# SparkFun_BadgerStick.net
KiCad netlist of a schematic drawn in EAGLE
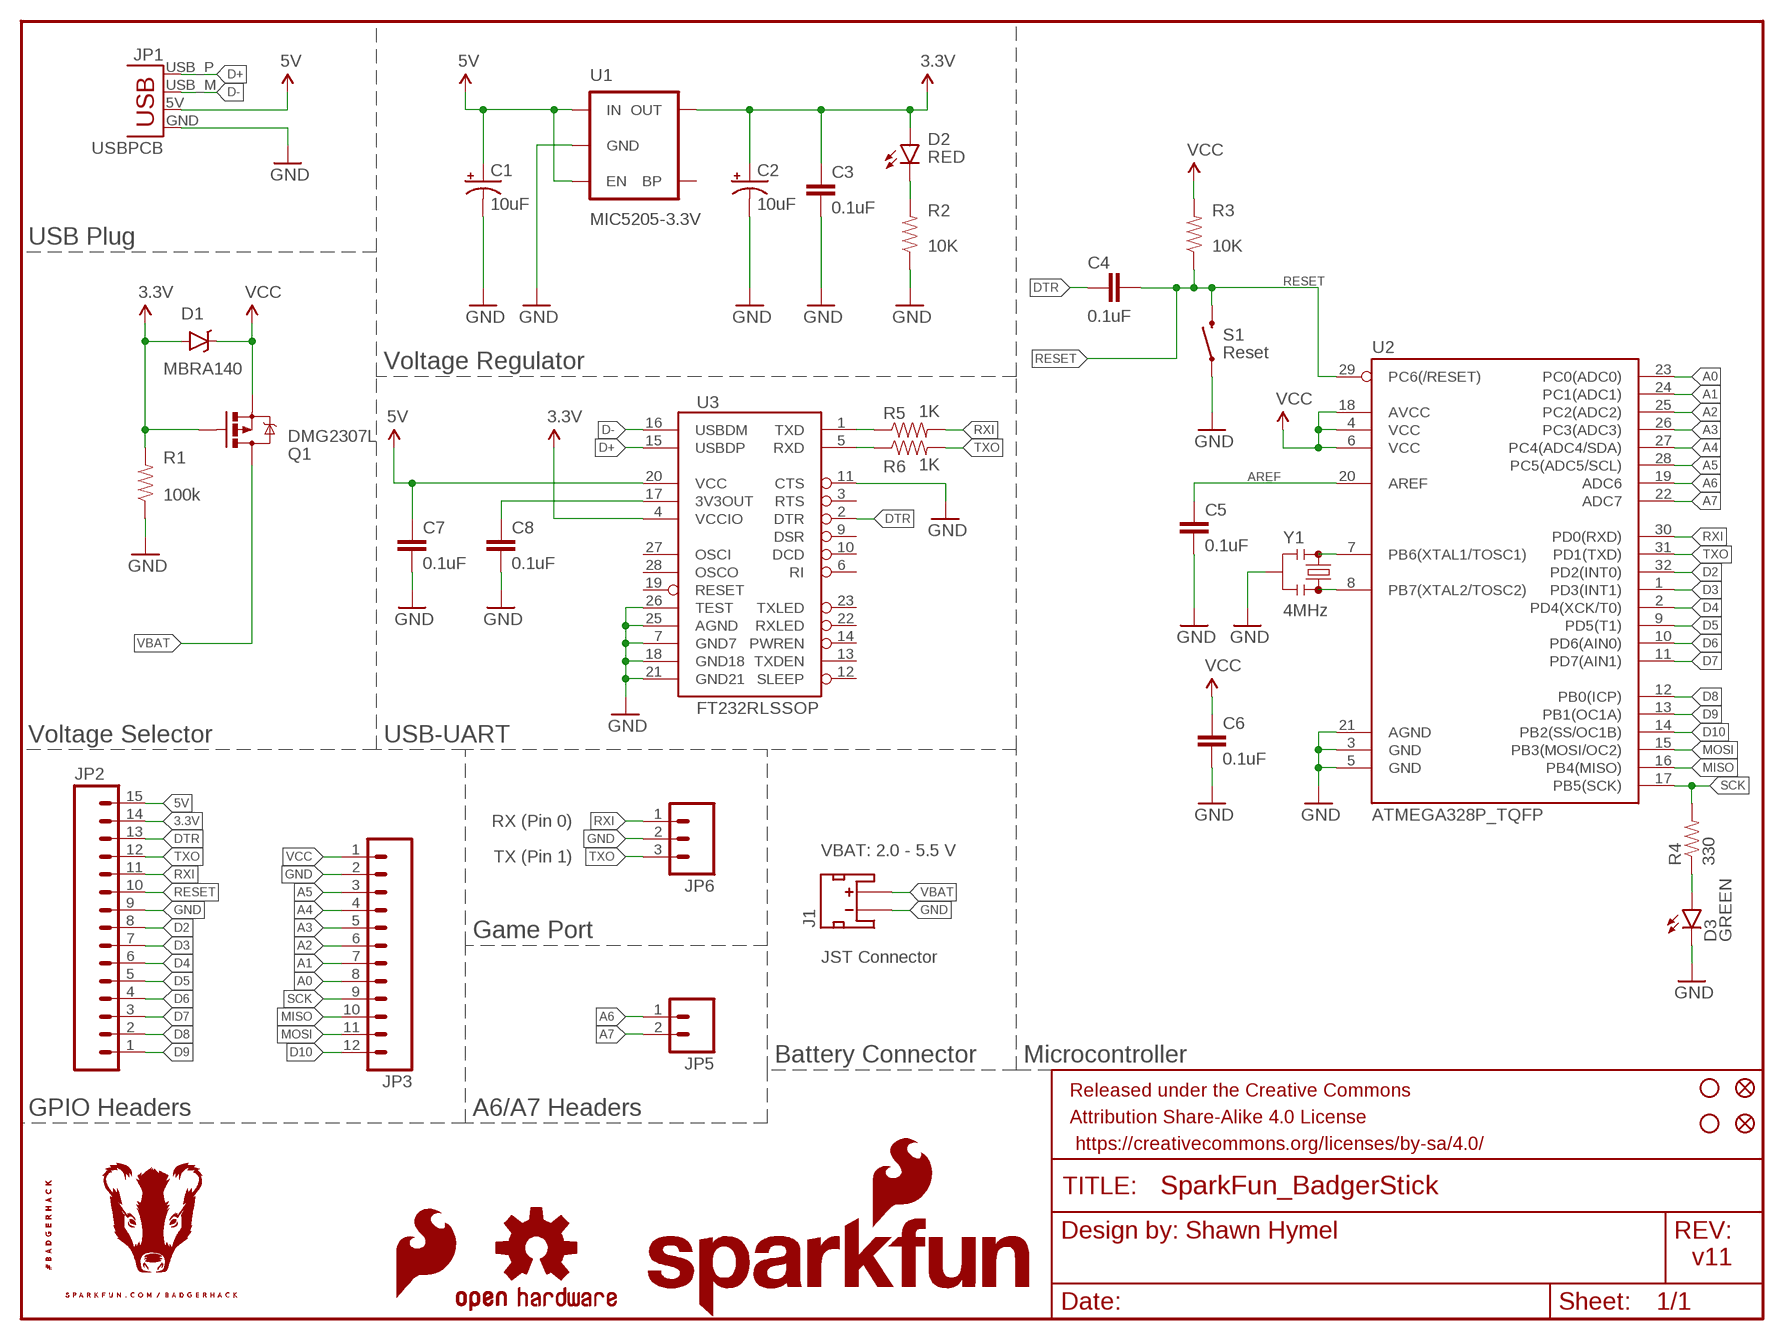
[diagram p0: schematic, sheet 1]

(export (version "E")
  (design (tool "Eeschema 10.0.6"))
  (components
    (comp (ref "C1")
      (value "10uF")
      (footprint "eagle-import:EIA3216")
      (libsource (lib "eagle-import") (part "10UF-16V-10%(TANT)"))
    )
    (comp (ref "C2")
      (value "10uF")
      (footprint "eagle-import:EIA3216")
      (libsource (lib "eagle-import") (part "10UF-16V-10%(TANT)"))
    )
    (comp (ref "C3")
      (value "0.1uF")
      (footprint "eagle-import:0603-CAP")
      (libsource (lib "eagle-import") (part "0.1UF-25V(+80/-20%)(0603)"))
    )
    (comp (ref "C4")
      (value "0.1uF")
      (footprint "eagle-import:0603-CAP")
      (libsource (lib "eagle-import") (part "0.1UF-25V(+80/-20%)(0603)"))
    )
    (comp (ref "C5")
      (value "0.1uF")
      (footprint "eagle-import:0603-CAP")
      (libsource (lib "eagle-import") (part "0.1UF-25V(+80/-20%)(0603)"))
    )
    (comp (ref "C6")
      (value "0.1uF")
      (footprint "eagle-import:0603-CAP")
      (libsource (lib "eagle-import") (part "0.1UF-25V(+80/-20%)(0603)"))
    )
    (comp (ref "C7")
      (value "0.1uF")
      (footprint "eagle-import:0603-CAP")
      (libsource (lib "eagle-import") (part "0.1UF-25V(+80/-20%)(0603)"))
    )
    (comp (ref "C8")
      (value "0.1uF")
      (footprint "eagle-import:0603-CAP")
      (libsource (lib "eagle-import") (part "0.1UF-25V(+80/-20%)(0603)"))
    )
    (comp (ref "D1")
      (value "MBRA140")
      (footprint "eagle-import:SMA-DIODE")
      (libsource (lib "eagle-import") (part "DIODE-SCHOTTKY-MBRA140"))
    )
    (comp (ref "D2")
      (value "RED")
      (footprint "eagle-import:LED-0603")
      (libsource (lib "eagle-import") (part "LED-RED0603"))
    )
    (comp (ref "D3")
      (value "GREEN")
      (footprint "eagle-import:LED-0603")
      (libsource (lib "eagle-import") (part "LED-GREEN0603"))
    )
    (comp (ref "FID1")
      (value "FIDUCIAL1X2")
      (footprint "eagle-import:FIDUCIAL-1X2")
      (libsource (lib "eagle-import") (part "FIDUCIAL1X2"))
    )
    (comp (ref "FID2")
      (value "FIDUCIAL1X2")
      (footprint "eagle-import:FIDUCIAL-1X2")
      (libsource (lib "eagle-import") (part "FIDUCIAL1X2"))
    )
    (comp (ref "FRAME1")
      (value "FRAME-LETTER")
      (footprint "eagle-import:CREATIVE_COMMONS")
      (fields
        (field (name "DESIGNER") "NAME")
        (field (name "VERSION") "v01")
        (field (name "DESIGNER_1") "Shawn Hymel")
        (field (name "VERSION_1") "v11")
      )
      (libsource (lib "eagle-import") (part "FRAME-LETTER"))
    )
    (comp (ref "J1")
      (value "JST_2MM_MALE")
      (footprint "eagle-import:JST-2-SMD")
      (libsource (lib "eagle-import") (part "JST_2MM_MALE"))
    )
    (comp (ref "JP1")
      (value "USBPCB")
      (footprint "eagle-import:USB-A-PCB")
      (libsource (lib "eagle-import") (part "USBPCB"))
    )
    (comp (ref "JP2")
      (value "M15LOCK_NO_SILK")
      (footprint "eagle-import:1X15_LOCK_NO_SILK")
      (libsource (lib "eagle-import") (part "M15LOCK_NO_SILK"))
    )
    (comp (ref "JP3")
      (value "M12LOCK_NO_SILK")
      (footprint "eagle-import:1X12_LOCK_NO_SILK")
      (libsource (lib "eagle-import") (part "M12LOCK_NO_SILK"))
    )
    (comp (ref "JP5")
      (value "M021X02_NO_SILK")
      (footprint "eagle-import:1X02_NO_SILK")
      (libsource (lib "eagle-import") (part "M021X02_NO_SILK"))
    )
    (comp (ref "JP6")
      (value "M03LOCK Female")
      (footprint "eagle-import:1X03_LOCK_NO_SILK")
      (libsource (lib "eagle-import") (part "M03LOCK_NO_SILK"))
    )
    (comp (ref "LOGO1")
      (value "SFE_LOGO_FLAME.1_INCH")
      (footprint "eagle-import:SFE_LOGO_FLAME_.1")
      (libsource (lib "eagle-import") (part "SFE_LOGO_FLAME.1_INCH"))
    )
    (comp (ref "LOGO2")
      (value "OSHW-LOGOS")
      (footprint "eagle-import:OSHW-LOGO-S")
      (libsource (lib "eagle-import") (part "OSHW-LOGOS"))
    )
    (comp (ref "Q1")
      (value "DMG2307L")
      (footprint "eagle-import:SOT23-3")
      (libsource (lib "eagle-import") (part "MOSFET-PCHANNELDMG2307L"))
    )
    (comp (ref "R1")
      (value "100k")
      (footprint "eagle-import:0603-RES")
      (libsource (lib "eagle-import") (part "100KOHM-1/10W-1%(0603)"))
    )
    (comp (ref "R2")
      (value "10K")
      (footprint "eagle-import:0603-RES")
      (libsource (lib "eagle-import") (part "10KOHM-1/10W-1%(0603)0603"))
    )
    (comp (ref "R3")
      (value "10K")
      (footprint "eagle-import:0603-RES")
      (libsource (lib "eagle-import") (part "10KOHM-1/10W-1%(0603)0603"))
    )
    (comp (ref "R4")
      (value "330")
      (footprint "eagle-import:0603-RES")
      (libsource (lib "eagle-import") (part "330OHM1/10W1%(0603)"))
    )
    (comp (ref "R5")
      (value "1K")
      (footprint "eagle-import:0603-RES")
      (libsource (lib "eagle-import") (part "1KOHM-1/10W-1%(0603)"))
    )
    (comp (ref "R6")
      (value "1K")
      (footprint "eagle-import:0603-RES")
      (libsource (lib "eagle-import") (part "1KOHM-1/10W-1%(0603)"))
    )
    (comp (ref "S1")
      (value "SWITCH-MOMENTARY-2SMD-REDUNDANT")
      (footprint "eagle-import:TACTILE-SWITCH-SMD")
      (fields (field (name "FUNC") "Reset"))
      (libsource (lib "eagle-import") (part "SWITCH-MOMENTARY-2SMD-REDUNDANT"))
    )
    (comp (ref "STANDOFF1")
      (value "STAND-OFF")
      (footprint "eagle-import:STAND-OFF")
      (libsource (lib "eagle-import") (part "STAND-OFF"))
    )
    (comp (ref "STANDOFF2")
      (value "STAND-OFF")
      (footprint "eagle-import:STAND-OFF")
      (libsource (lib "eagle-import") (part "STAND-OFF"))
    )
    (comp (ref "U$1")
      (value "SFE_LOGO_NAME_FLAME.1_INCH")
      (footprint "eagle-import:SFE_LOGO_NAME_FLAME_.1")
      (libsource (lib "eagle-import") (part "SFE_LOGO_NAME_FLAME.1_INCH"))
    )
    (comp (ref "U$2")
      (value "BADGERHACK_LOGODUMMY")
      (footprint "eagle-import:DUMMY")
      (libsource (lib "eagle-import") (part "BADGERHACK_LOGODUMMY"))
    )
    (comp (ref "U1")
      (value "MIC5205-3.3V")
      (footprint "eagle-import:SOT23-5")
      (libsource (lib "eagle-import") (part "MIC52053.3V"))
    )
    (comp (ref "U2")
      (value "ATMEGA328P_TQFP")
      (footprint "eagle-import:TQFP32-08")
      (libsource (lib "eagle-import") (part "ATMEGA328P_TQFP"))
    )
    (comp (ref "U3")
      (value "FT232RLSSOP")
      (footprint "eagle-import:SSOP28DB")
      (libsource (lib "eagle-import") (part "FT232RLSSOP"))
    )
    (comp (ref "Y1")
      (value "4MHz")
      (footprint "eagle-import:RESONATOR-SMD_MED")
      (libsource (lib "eagle-import") (part "RESONATOR4MHZ"))
    )
  )
  (nets
    (net (code "1") (name "/AREF") (class "Default")
      (node (ref "C5") (pin "1") (pinfunction "1_1") (pintype "passive"))
      (node (ref "U2") (pin "20") (pinfunction "AREF_20") (pintype "bidirectional"))
    )
    (net (code "2") (name "3.3V") (class "Default")
      (node (ref "C2") (pin "A") (pinfunction "+_A") (pintype "passive"))
      (node (ref "C3") (pin "1") (pinfunction "1_1") (pintype "passive"))
      (node (ref "D1") (pin "A") (pinfunction "A_A") (pintype "passive"))
      (node (ref "D2") (pin "A") (pinfunction "A_A") (pintype "passive"))
      (node (ref "JP2") (pin "14") (pinfunction "14_14") (pintype "passive"))
      (node (ref "Q1") (pin "1") (pinfunction "G_1") (pintype "passive"))
      (node (ref "R1") (pin "2") (pinfunction "2_2") (pintype "passive"))
      (node (ref "U1") (pin "5") (pinfunction "OUT_5") (pintype "passive"))
      (node (ref "U3") (pin "4") (pinfunction "VCCIO_4") (pintype "power_in"))
    )
    (net (code "3") (name "5V") (class "Default")
      (node (ref "C1") (pin "A") (pinfunction "+_A") (pintype "passive"))
      (node (ref "C7") (pin "1") (pinfunction "1_1") (pintype "passive"))
      (node (ref "JP1") (pin "5V") (pinfunction "VBUS_5V") (pintype "bidirectional"))
      (node (ref "JP2") (pin "15") (pinfunction "15_15") (pintype "passive"))
      (node (ref "U1") (pin "1") (pinfunction "IN_1") (pintype "input"))
      (node (ref "U1") (pin "3") (pinfunction "EN_3") (pintype "input"))
      (node (ref "U3") (pin "20") (pinfunction "VCC_20") (pintype "power_in"))
    )
    (net (code "4") (name "A0") (class "Default")
      (node (ref "JP3") (pin "8") (pinfunction "8_8") (pintype "passive"))
      (node (ref "U2") (pin "23") (pinfunction "PC0(ADC0)_23") (pintype "bidirectional"))
    )
    (net (code "5") (name "A1") (class "Default")
      (node (ref "JP3") (pin "7") (pinfunction "7_7") (pintype "passive"))
      (node (ref "U2") (pin "24") (pinfunction "PC1(ADC1)_24") (pintype "bidirectional"))
    )
    (net (code "6") (name "A2") (class "Default")
      (node (ref "JP3") (pin "6") (pinfunction "6_6") (pintype "passive"))
      (node (ref "U2") (pin "25") (pinfunction "PC2(ADC2)_25") (pintype "bidirectional"))
    )
    (net (code "7") (name "A3") (class "Default")
      (node (ref "JP3") (pin "5") (pinfunction "5_5") (pintype "passive"))
      (node (ref "U2") (pin "26") (pinfunction "PC3(ADC3)_26") (pintype "bidirectional"))
    )
    (net (code "8") (name "A4") (class "Default")
      (node (ref "JP3") (pin "4") (pinfunction "4_4") (pintype "passive"))
      (node (ref "U2") (pin "27") (pinfunction "PC4(ADC4/SDA)_27") (pintype "bidirectional"))
    )
    (net (code "9") (name "A5") (class "Default")
      (node (ref "JP3") (pin "3") (pinfunction "3_3") (pintype "passive"))
      (node (ref "U2") (pin "28") (pinfunction "PC5(ADC5/SCL)_28") (pintype "bidirectional"))
    )
    (net (code "10") (name "A6") (class "Default")
      (node (ref "JP5") (pin "1") (pinfunction "1_1") (pintype "passive"))
      (node (ref "U2") (pin "19") (pinfunction "ADC6_19") (pintype "bidirectional"))
    )
    (net (code "11") (name "A7") (class "Default")
      (node (ref "JP5") (pin "2") (pinfunction "2_2") (pintype "passive"))
      (node (ref "U2") (pin "22") (pinfunction "ADC7_22") (pintype "bidirectional"))
    )
    (net (code "12") (name "D+") (class "Default")
      (node (ref "JP1") (pin "USB_P") (pinfunction "D+_USB_P") (pintype "bidirectional"))
      (node (ref "U3") (pin "15") (pinfunction "USBDP_15") (pintype "bidirectional"))
    )
    (net (code "13") (name "D-") (class "Default")
      (node (ref "JP1") (pin "USB_M") (pinfunction "D-_USB_M") (pintype "bidirectional"))
      (node (ref "U3") (pin "16") (pinfunction "USBDM_16") (pintype "bidirectional"))
    )
    (net (code "14") (name "D2") (class "Default")
      (node (ref "JP2") (pin "8") (pinfunction "8_8") (pintype "passive"))
      (node (ref "U2") (pin "32") (pinfunction "PD2(INT0)_32") (pintype "bidirectional"))
    )
    (net (code "15") (name "D3") (class "Default")
      (node (ref "JP2") (pin "7") (pinfunction "7_7") (pintype "passive"))
      (node (ref "U2") (pin "1") (pinfunction "PD3(INT1)_1") (pintype "bidirectional"))
    )
    (net (code "16") (name "D4") (class "Default")
      (node (ref "JP2") (pin "6") (pinfunction "6_6") (pintype "passive"))
      (node (ref "U2") (pin "2") (pinfunction "PD4(XCK/T0)_2") (pintype "bidirectional"))
    )
    (net (code "17") (name "D5") (class "Default")
      (node (ref "JP2") (pin "5") (pinfunction "5_5") (pintype "passive"))
      (node (ref "U2") (pin "9") (pinfunction "PD5(T1)_9") (pintype "bidirectional"))
    )
    (net (code "18") (name "D6") (class "Default")
      (node (ref "JP2") (pin "4") (pinfunction "4_4") (pintype "passive"))
      (node (ref "U2") (pin "10") (pinfunction "PD6(AIN0)_10") (pintype "bidirectional"))
    )
    (net (code "19") (name "D7") (class "Default")
      (node (ref "JP2") (pin "3") (pinfunction "3_3") (pintype "passive"))
      (node (ref "U2") (pin "11") (pinfunction "PD7(AIN1)_11") (pintype "bidirectional"))
    )
    (net (code "20") (name "D8") (class "Default")
      (node (ref "JP2") (pin "2") (pinfunction "2_2") (pintype "passive"))
      (node (ref "U2") (pin "12") (pinfunction "PB0(ICP)_12") (pintype "bidirectional"))
    )
    (net (code "21") (name "D9") (class "Default")
      (node (ref "JP2") (pin "1") (pinfunction "1_1") (pintype "passive"))
      (node (ref "U2") (pin "13") (pinfunction "PB1(OC1A)_13") (pintype "bidirectional"))
    )
    (net (code "22") (name "D10") (class "Default")
      (node (ref "JP3") (pin "12") (pinfunction "12_12") (pintype "passive"))
      (node (ref "U2") (pin "14") (pinfunction "PB2(SS/OC1B)_14") (pintype "bidirectional"))
    )
    (net (code "23") (name "DTR") (class "Default")
      (node (ref "C4") (pin "1") (pinfunction "1_1") (pintype "passive"))
      (node (ref "JP2") (pin "13") (pinfunction "13_13") (pintype "passive"))
      (node (ref "U3") (pin "2") (pinfunction "DTR_2") (pintype "output"))
    )
    (net (code "24") (name "GND") (class "Default")
      (node (ref "C1") (pin "C") (pinfunction "-_C") (pintype "passive"))
      (node (ref "C2") (pin "C") (pinfunction "-_C") (pintype "passive"))
      (node (ref "C3") (pin "2") (pinfunction "2_2") (pintype "passive"))
      (node (ref "C5") (pin "2") (pinfunction "2_2") (pintype "passive"))
      (node (ref "C6") (pin "2") (pinfunction "2_2") (pintype "passive"))
      (node (ref "C7") (pin "2") (pinfunction "2_2") (pintype "passive"))
      (node (ref "C8") (pin "2") (pinfunction "2_2") (pintype "passive"))
      (node (ref "D3") (pin "C") (pinfunction "C_C") (pintype "passive"))
      (node (ref "J1") (pin "1") (pinfunction "-_1") (pintype "bidirectional"))
      (node (ref "JP1") (pin "GND") (pinfunction "GND_GND") (pintype "bidirectional"))
      (node (ref "JP2") (pin "9") (pinfunction "9_9") (pintype "passive"))
      (node (ref "JP3") (pin "2") (pinfunction "2_2") (pintype "passive"))
      (node (ref "JP6") (pin "2") (pinfunction "2_2") (pintype "passive"))
      (node (ref "R1") (pin "1") (pinfunction "1_1") (pintype "passive"))
      (node (ref "R2") (pin "1") (pinfunction "1_1") (pintype "passive"))
      (node (ref "S1") (pin "1") (pinfunction "1_1") (pintype "passive"))
      (node (ref "S1") (pin "2") (pinfunction "1_2") (pintype "passive"))
      (node (ref "U1") (pin "2") (pinfunction "GND_2") (pintype "input"))
      (node (ref "U2") (pin "21") (pinfunction "AGND_21") (pintype "bidirectional"))
      (node (ref "U2") (pin "3") (pinfunction "GND_3") (pintype "bidirectional"))
      (node (ref "U2") (pin "5") (pinfunction "GND_5") (pintype "bidirectional"))
      (node (ref "U3") (pin "11") (pinfunction "CTS_11") (pintype "input"))
      (node (ref "U3") (pin "18") (pinfunction "GND18_18") (pintype "power_in"))
      (node (ref "U3") (pin "21") (pinfunction "GND21_21") (pintype "power_in"))
      (node (ref "U3") (pin "25") (pinfunction "AGND_25") (pintype "power_in"))
      (node (ref "U3") (pin "26") (pinfunction "TEST_26") (pintype "input"))
      (node (ref "U3") (pin "7") (pinfunction "GND7_7") (pintype "power_in"))
      (node (ref "Y1") (pin "2") (pinfunction "2_2") (pintype "passive"))
    )
    (net (code "25") (name "MISO") (class "Default")
      (node (ref "JP3") (pin "10") (pinfunction "10_10") (pintype "passive"))
      (node (ref "U2") (pin "16") (pinfunction "PB4(MISO)_16") (pintype "bidirectional"))
    )
    (net (code "26") (name "MOSI") (class "Default")
      (node (ref "JP3") (pin "11") (pinfunction "11_11") (pintype "passive"))
      (node (ref "U2") (pin "15") (pinfunction "PB3(MOSI/OC2)_15") (pintype "bidirectional"))
    )
    (net (code "27") (name "Net-(D2-PadC)") (class "Default")
      (node (ref "D2") (pin "C") (pinfunction "C_C") (pintype "passive"))
      (node (ref "R2") (pin "2") (pinfunction "2_2") (pintype "passive"))
    )
    (net (code "28") (name "Net-(D3-PadA)") (class "Default")
      (node (ref "D3") (pin "A") (pinfunction "A_A") (pintype "passive"))
      (node (ref "R4") (pin "1") (pinfunction "1_1") (pintype "passive"))
    )
    (net (code "29") (name "Net-(U2-PB6(XTAL1{slash}TOSC1))") (class "Default")
      (node (ref "U2") (pin "7") (pinfunction "PB6(XTAL1/TOSC1)_7") (pintype "bidirectional"))
      (node (ref "Y1") (pin "1") (pinfunction "1_1") (pintype "passive"))
    )
    (net (code "30") (name "Net-(U2-PB7(XTAL2{slash}TOSC2))") (class "Default")
      (node (ref "U2") (pin "8") (pinfunction "PB7(XTAL2/TOSC2)_8") (pintype "bidirectional"))
      (node (ref "Y1") (pin "3") (pinfunction "3_3") (pintype "passive"))
    )
    (net (code "31") (name "Net-(U3-3V3OUT)") (class "Default")
      (node (ref "C8") (pin "1") (pinfunction "1_1") (pintype "passive"))
      (node (ref "U3") (pin "17") (pinfunction "3V3OUT_17") (pintype "output"))
    )
    (net (code "32") (name "Net-(U3-RXD)") (class "Default")
      (node (ref "R6") (pin "1") (pinfunction "1_1") (pintype "passive"))
      (node (ref "U3") (pin "5") (pinfunction "RXD_5") (pintype "input"))
    )
    (net (code "33") (name "Net-(U3-TXD)") (class "Default")
      (node (ref "R5") (pin "1") (pinfunction "1_1") (pintype "passive"))
      (node (ref "U3") (pin "1") (pinfunction "TXD_1") (pintype "output"))
    )
    (net (code "34") (name "RESET") (class "Default")
      (node (ref "C4") (pin "2") (pinfunction "2_2") (pintype "passive"))
      (node (ref "JP2") (pin "10") (pinfunction "10_10") (pintype "passive"))
      (node (ref "R3") (pin "1") (pinfunction "1_1") (pintype "passive"))
      (node (ref "S1") (pin "3") (pinfunction "2_3") (pintype "passive"))
      (node (ref "S1") (pin "4") (pinfunction "2_4") (pintype "passive"))
      (node (ref "U2") (pin "29") (pinfunction "PC6(/RESET)_29") (pintype "bidirectional"))
    )
    (net (code "35") (name "RXI") (class "Default")
      (node (ref "JP2") (pin "11") (pinfunction "11_11") (pintype "passive"))
      (node (ref "JP6") (pin "1") (pinfunction "1_1") (pintype "passive"))
      (node (ref "R5") (pin "2") (pinfunction "2_2") (pintype "passive"))
      (node (ref "U2") (pin "30") (pinfunction "PD0(RXD)_30") (pintype "bidirectional"))
    )
    (net (code "36") (name "SCK") (class "Default")
      (node (ref "JP3") (pin "9") (pinfunction "9_9") (pintype "passive"))
      (node (ref "R4") (pin "2") (pinfunction "2_2") (pintype "passive"))
      (node (ref "U2") (pin "17") (pinfunction "PB5(SCK)_17") (pintype "bidirectional"))
    )
    (net (code "37") (name "TXO") (class "Default")
      (node (ref "JP2") (pin "12") (pinfunction "12_12") (pintype "passive"))
      (node (ref "JP6") (pin "3") (pinfunction "3_3") (pintype "passive"))
      (node (ref "R6") (pin "2") (pinfunction "2_2") (pintype "passive"))
      (node (ref "U2") (pin "31") (pinfunction "PD1(TXD)_31") (pintype "bidirectional"))
    )
    (net (code "38") (name "VBAT") (class "Default")
      (node (ref "J1") (pin "2") (pinfunction "+_2") (pintype "bidirectional"))
      (node (ref "Q1") (pin "3") (pinfunction "D_3") (pintype "passive"))
    )
    (net (code "39") (name "VCC") (class "Default")
      (node (ref "C6") (pin "1") (pinfunction "1_1") (pintype "passive"))
      (node (ref "D1") (pin "C") (pinfunction "C_C") (pintype "passive"))
      (node (ref "JP3") (pin "1") (pinfunction "1_1") (pintype "passive"))
      (node (ref "Q1") (pin "2") (pinfunction "S_2") (pintype "passive"))
      (node (ref "R3") (pin "2") (pinfunction "2_2") (pintype "passive"))
      (node (ref "U2") (pin "18") (pinfunction "AVCC_18") (pintype "bidirectional"))
      (node (ref "U2") (pin "4") (pinfunction "VCC_4") (pintype "bidirectional"))
      (node (ref "U2") (pin "6") (pinfunction "VCC_6") (pintype "bidirectional"))
    )
    (net (code "40") (name "unconnected-(J1-PAD1-PadNC1)") (class "Default")
      (node (ref "J1") (pin "NC1") (pinfunction "PAD1_NC1") (pintype "bidirectional"))
    )
    (net (code "41") (name "unconnected-(J1-PAD2-PadNC2)") (class "Default")
      (node (ref "J1") (pin "NC2") (pinfunction "PAD2_NC2") (pintype "bidirectional"))
    )
    (net (code "42") (name "unconnected-(U1-BP-Pad4)") (class "Default")
      (node (ref "U1") (pin "4") (pinfunction "BP_4") (pintype "input"))
    )
    (net (code "43") (name "unconnected-(U3-DCD-Pad10)") (class "Default")
      (node (ref "U3") (pin "10") (pinfunction "DCD_10") (pintype "input"))
    )
    (net (code "44") (name "unconnected-(U3-DSR-Pad9)") (class "Default")
      (node (ref "U3") (pin "9") (pinfunction "DSR_9") (pintype "input"))
    )
    (net (code "45") (name "unconnected-(U3-OSCI-Pad27)") (class "Default")
      (node (ref "U3") (pin "27") (pinfunction "OSCI_27") (pintype "input"))
    )
    (net (code "46") (name "unconnected-(U3-OSCO-Pad28)") (class "Default")
      (node (ref "U3") (pin "28") (pinfunction "OSCO_28") (pintype "output"))
    )
    (net (code "47") (name "unconnected-(U3-PWREN-Pad14)") (class "Default")
      (node (ref "U3") (pin "14") (pinfunction "PWREN_14") (pintype "input"))
    )
    (net (code "48") (name "unconnected-(U3-RESET-Pad19)") (class "Default")
      (node (ref "U3") (pin "19") (pinfunction "RESET_19") (pintype "input"))
    )
    (net (code "49") (name "unconnected-(U3-RI-Pad6)") (class "Default")
      (node (ref "U3") (pin "6") (pinfunction "RI_6") (pintype "input"))
    )
    (net (code "50") (name "unconnected-(U3-RTS-Pad3)") (class "Default")
      (node (ref "U3") (pin "3") (pinfunction "RTS_3") (pintype "output"))
    )
    (net (code "51") (name "unconnected-(U3-RXLED-Pad22)") (class "Default")
      (node (ref "U3") (pin "22") (pinfunction "RXLED_22") (pintype "input"))
    )
    (net (code "52") (name "unconnected-(U3-SLEEP-Pad12)") (class "Default")
      (node (ref "U3") (pin "12") (pinfunction "SLEEP_12") (pintype "input"))
    )
    (net (code "53") (name "unconnected-(U3-TXDEN-Pad13)") (class "Default")
      (node (ref "U3") (pin "13") (pinfunction "TXDEN_13") (pintype "input"))
    )
    (net (code "54") (name "unconnected-(U3-TXLED-Pad23)") (class "Default")
      (node (ref "U3") (pin "23") (pinfunction "TXLED_23") (pintype "input"))
    )
  )
)
